# BareBonesArduino.net
KiCad netlist of a schematic drawn in EAGLE
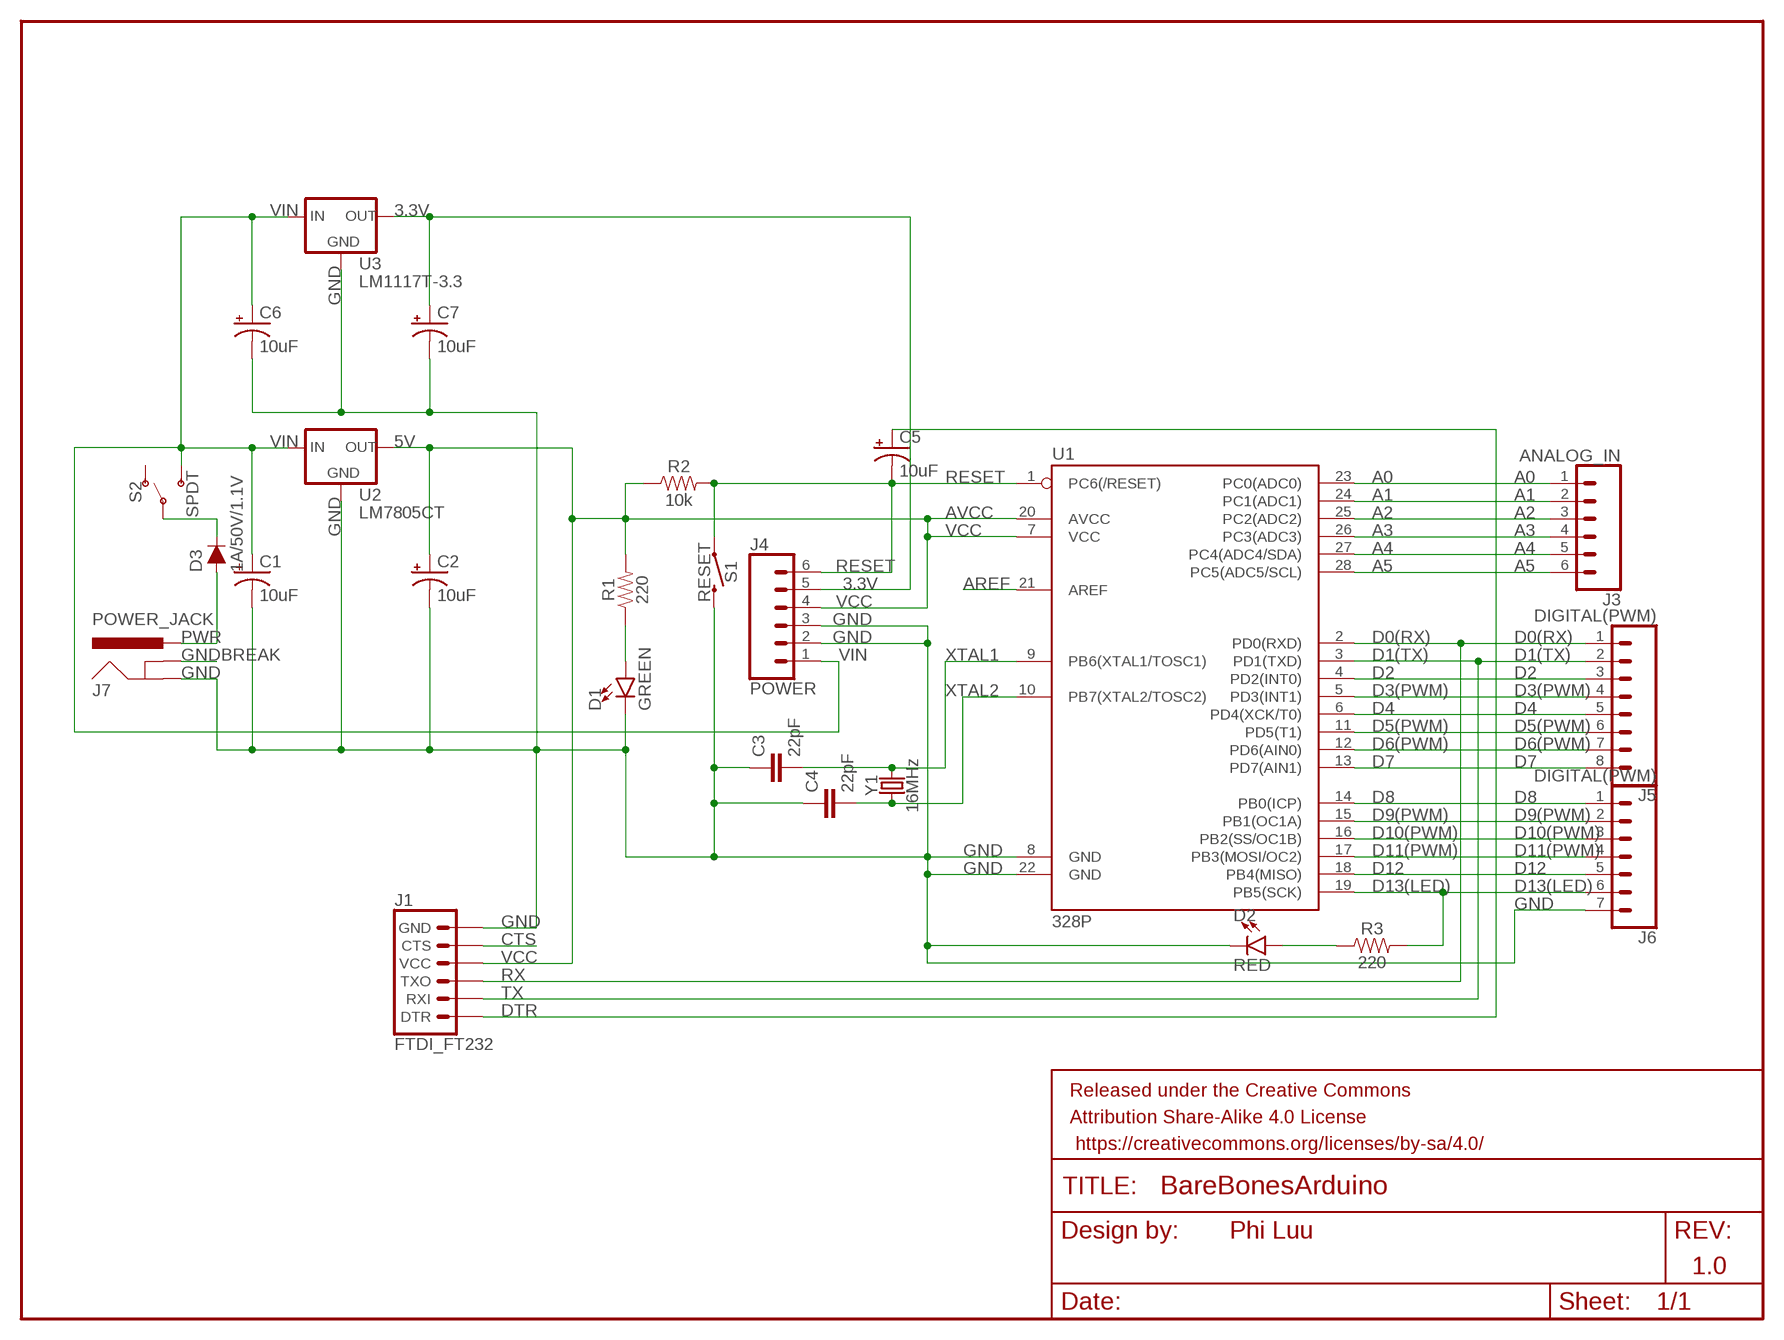
[diagram p0: schematic, sheet 1]

(export (version "E")
  (design (tool "Eeschema 10.0.6"))
  (components
    (comp (ref "C1")
      (value "10uF")
      (footprint "eagle-import:CPOL-RADIAL-2.5MM-5MM")
      (libsource (lib "eagle-import") (part "10UF-POLAR-RADIAL-2.5MM-25V-20%"))
    )
    (comp (ref "C2")
      (value "10uF")
      (footprint "eagle-import:CPOL-RADIAL-2.5MM-5MM")
      (libsource (lib "eagle-import") (part "10UF-POLAR-RADIAL-2.5MM-25V-20%"))
    )
    (comp (ref "C3")
      (value "22pF")
      (footprint "eagle-import:CAP-PTH-2.54")
      (libsource (lib "eagle-import") (part "22PF-PTH-2.54MM-200V-5%"))
    )
    (comp (ref "C4")
      (value "22pF")
      (footprint "eagle-import:CAP-PTH-2.54")
      (libsource (lib "eagle-import") (part "22PF-PTH-2.54MM-200V-5%"))
    )
    (comp (ref "C5")
      (value "10uF")
      (footprint "eagle-import:CPOL-RADIAL-2.5MM-5MM")
      (libsource (lib "eagle-import") (part "10UF-POLAR-RADIAL-2.5MM-25V-20%"))
    )
    (comp (ref "C6")
      (value "10uF")
      (footprint "eagle-import:CPOL-RADIAL-2.5MM-5MM")
      (libsource (lib "eagle-import") (part "10UF-POLAR-RADIAL-2.5MM-25V-20%"))
    )
    (comp (ref "C7")
      (value "10uF")
      (footprint "eagle-import:CPOL-RADIAL-2.5MM-5MM")
      (libsource (lib "eagle-import") (part "10UF-POLAR-RADIAL-2.5MM-25V-20%"))
    )
    (comp (ref "D1")
      (value "GREEN")
      (footprint "eagle-import:LED_5MM")
      (libsource (lib "eagle-import") (part "LED5MM"))
    )
    (comp (ref "D2")
      (value "RED")
      (footprint "eagle-import:LED_5MM")
      (libsource (lib "eagle-import") (part "LED5MM"))
    )
    (comp (ref "D3")
      (value "1A/50V/1.1V")
      (footprint "eagle-import:DIODE-1N4001")
      (libsource (lib "eagle-import") (part "DIODE-PTH"))
    )
    (comp (ref "FRAME1")
      (value "FRAME-LETTER")
      (footprint "eagle-import:CREATIVE_COMMONS")
      (libsource (lib "eagle-import") (part "FRAME-LETTER"))
    )
    (comp (ref "J1")
      (value "FTDI_FT232")
      (footprint "eagle-import:1X06")
      (libsource (lib "eagle-import") (part "6_PIN_SERIAL_TARGET"))
    )
    (comp (ref "J3")
      (value "ANALOG_IN")
      (footprint "eagle-import:1X06")
      (libsource (lib "eagle-import") (part "CONN_06SILK_FEMALE_PTH"))
    )
    (comp (ref "J4")
      (value "POWER")
      (footprint "eagle-import:1X06")
      (libsource (lib "eagle-import") (part "CONN_06SILK_FEMALE_PTH"))
    )
    (comp (ref "J5")
      (value "DIGITAL(PWM)")
      (footprint "eagle-import:1X08")
      (libsource (lib "eagle-import") (part "CONN_08{dblquote}"))
    )
    (comp (ref "J6")
      (value "DIGITAL(PWM)")
      (footprint "eagle-import:1X07")
      (libsource (lib "eagle-import") (part "CONN_07"))
    )
    (comp (ref "J7")
      (value "POWER_JACK")
      (footprint "eagle-import:POWER_JACK_PTH")
      (libsource (lib "eagle-import") (part "POWER_JACK"))
    )
    (comp (ref "R1")
      (value "220")
      (footprint "eagle-import:AXIAL-0.3")
      (libsource (lib "eagle-import") (part "1KOHM-HORIZ-1/4W-5%"))
    )
    (comp (ref "R2")
      (value "10k")
      (footprint "eagle-import:AXIAL-0.3")
      (libsource (lib "eagle-import") (part "10KOHM-HORIZ-1/4W-5%"))
    )
    (comp (ref "R3")
      (value "220")
      (footprint "eagle-import:AXIAL-0.3")
      (libsource (lib "eagle-import") (part "1KOHM-HORIZ-1/4W-5%"))
    )
    (comp (ref "S1")
      (value "RESET")
      (footprint "eagle-import:TACTILE_SWITCH_PTH_6.0MM")
      (libsource (lib "eagle-import") (part "MOMENTARY-SWITCH-SPST-PTH-6.0MM"))
    )
    (comp (ref "S2")
      (value "SPDT")
      (footprint "eagle-import:SWITCH_SPDT_PTH_11.6X4.0MM")
      (libsource (lib "eagle-import") (part "SWITCH-SPDT-PTH-11.6X4.0MM"))
    )
    (comp (ref "U1")
      (value "328P")
      (footprint "eagle-import:DIP28")
      (libsource (lib "eagle-import") (part "ATMEGA328P_PDIP"))
    )
    (comp (ref "U2")
      (value "LM7805CT")
      (footprint "eagle-import:TO-220-ALT")
      (libsource (lib "eagle-import") (part "V_REG_78XX-TO-220"))
    )
    (comp (ref "U3")
      (value "LM1117T-3.3")
      (footprint "eagle-import:78XXL")
      (libsource (lib "eagle-import") (part "V_REG_LD1117VXX"))
    )
    (comp (ref "Y1")
      (value "16MHz")
      (footprint "eagle-import:HC49US")
      (libsource (lib "eagle-import") (part "CRYSTAL-16MHZPTH-HC49US"))
    )
  )
  (nets
    (net (code "1") (name "/3.3V") (class "Default")
      (node (ref "C7") (pin "1") (pinfunction "+_1") (pintype "passive"))
      (node (ref "J4") (pin "5") (pinfunction "5_5") (pintype "passive"))
      (node (ref "U3") (pin "GND") (pinfunction "OUT_GND") (pintype "passive"))
    )
    (net (code "2") (name "/A0") (class "Default")
      (node (ref "J3") (pin "1") (pinfunction "1_1") (pintype "passive"))
      (node (ref "U1") (pin "23") (pinfunction "PC0(ADC0)_23") (pintype "bidirectional"))
    )
    (net (code "3") (name "/A1") (class "Default")
      (node (ref "J3") (pin "2") (pinfunction "2_2") (pintype "passive"))
      (node (ref "U1") (pin "24") (pinfunction "PC1(ADC1)_24") (pintype "bidirectional"))
    )
    (net (code "4") (name "/A2") (class "Default")
      (node (ref "J3") (pin "3") (pinfunction "3_3") (pintype "passive"))
      (node (ref "U1") (pin "25") (pinfunction "PC2(ADC2)_25") (pintype "bidirectional"))
    )
    (net (code "5") (name "/A3") (class "Default")
      (node (ref "J3") (pin "4") (pinfunction "4_4") (pintype "passive"))
      (node (ref "U1") (pin "26") (pinfunction "PC3(ADC3)_26") (pintype "bidirectional"))
    )
    (net (code "6") (name "/A4") (class "Default")
      (node (ref "J3") (pin "5") (pinfunction "5_5") (pintype "passive"))
      (node (ref "U1") (pin "27") (pinfunction "PC4(ADC4/SDA)_27") (pintype "bidirectional"))
    )
    (net (code "7") (name "/A5") (class "Default")
      (node (ref "J3") (pin "6") (pinfunction "6_6") (pintype "passive"))
      (node (ref "U1") (pin "28") (pinfunction "PC5(ADC5/SCL)_28") (pintype "bidirectional"))
    )
    (net (code "8") (name "/AREF") (class "Default")
      (node (ref "U1") (pin "21") (pinfunction "AREF_21") (pintype "bidirectional"))
    )
    (net (code "9") (name "/CTS") (class "Default")
      (node (ref "J1") (pin "5") (pinfunction "CTS_5") (pintype "passive"))
    )
    (net (code "10") (name "/D0(RX)") (class "Default")
      (node (ref "J1") (pin "3") (pinfunction "TXO_3") (pintype "passive"))
      (node (ref "J5") (pin "1") (pinfunction "1_1") (pintype "passive"))
      (node (ref "U1") (pin "2") (pinfunction "PD0(RXD)_2") (pintype "bidirectional"))
    )
    (net (code "11") (name "/D1(TX)") (class "Default")
      (node (ref "J1") (pin "2") (pinfunction "RXI_2") (pintype "passive"))
      (node (ref "J5") (pin "2") (pinfunction "2_2") (pintype "passive"))
      (node (ref "U1") (pin "3") (pinfunction "PD1(TXD)_3") (pintype "bidirectional"))
    )
    (net (code "12") (name "/D2") (class "Default")
      (node (ref "J5") (pin "3") (pinfunction "3_3") (pintype "passive"))
      (node (ref "U1") (pin "4") (pinfunction "PD2(INT0)_4") (pintype "bidirectional"))
    )
    (net (code "13") (name "/D3(PWM)") (class "Default")
      (node (ref "J5") (pin "4") (pinfunction "4_4") (pintype "passive"))
      (node (ref "U1") (pin "5") (pinfunction "PD3(INT1)_5") (pintype "bidirectional"))
    )
    (net (code "14") (name "/D4") (class "Default")
      (node (ref "J5") (pin "5") (pinfunction "5_5") (pintype "passive"))
      (node (ref "U1") (pin "6") (pinfunction "PD4(XCK/T0)_6") (pintype "bidirectional"))
    )
    (net (code "15") (name "/D5(PWM)") (class "Default")
      (node (ref "J5") (pin "6") (pinfunction "6_6") (pintype "passive"))
      (node (ref "U1") (pin "11") (pinfunction "PD5(T1)_11") (pintype "bidirectional"))
    )
    (net (code "16") (name "/D6(PWM)") (class "Default")
      (node (ref "J5") (pin "7") (pinfunction "7_7") (pintype "passive"))
      (node (ref "U1") (pin "12") (pinfunction "PD6(AIN0)_12") (pintype "bidirectional"))
    )
    (net (code "17") (name "/D7") (class "Default")
      (node (ref "J5") (pin "8") (pinfunction "8_8") (pintype "passive"))
      (node (ref "U1") (pin "13") (pinfunction "PD7(AIN1)_13") (pintype "bidirectional"))
    )
    (net (code "18") (name "/D8") (class "Default")
      (node (ref "J6") (pin "1") (pinfunction "1_1") (pintype "passive"))
      (node (ref "U1") (pin "14") (pinfunction "PB0(ICP)_14") (pintype "bidirectional"))
    )
    (net (code "19") (name "/D9(PWM)") (class "Default")
      (node (ref "J6") (pin "2") (pinfunction "2_2") (pintype "passive"))
      (node (ref "U1") (pin "15") (pinfunction "PB1(OC1A)_15") (pintype "bidirectional"))
    )
    (net (code "20") (name "/D10(PWM)") (class "Default")
      (node (ref "J6") (pin "3") (pinfunction "3_3") (pintype "passive"))
      (node (ref "U1") (pin "16") (pinfunction "PB2(SS/OC1B)_16") (pintype "bidirectional"))
    )
    (net (code "21") (name "/D11(PWM)") (class "Default")
      (node (ref "J6") (pin "4") (pinfunction "4_4") (pintype "passive"))
      (node (ref "U1") (pin "17") (pinfunction "PB3(MOSI/OC2)_17") (pintype "bidirectional"))
    )
    (net (code "22") (name "/D12") (class "Default")
      (node (ref "J6") (pin "5") (pinfunction "5_5") (pintype "passive"))
      (node (ref "U1") (pin "18") (pinfunction "PB4(MISO)_18") (pintype "bidirectional"))
    )
    (net (code "23") (name "/D13(LED)") (class "Default")
      (node (ref "J6") (pin "6") (pinfunction "6_6") (pintype "passive"))
      (node (ref "R3") (pin "P$2") (pinfunction "2_P$2") (pintype "passive"))
      (node (ref "U1") (pin "19") (pinfunction "PB5(SCK)_19") (pintype "bidirectional"))
    )
    (net (code "24") (name "/DTR") (class "Default")
      (node (ref "C5") (pin "1") (pinfunction "+_1") (pintype "passive"))
      (node (ref "J1") (pin "1") (pinfunction "DTR_1") (pintype "passive"))
    )
    (net (code "25") (name "/GND") (class "Default")
      (node (ref "C1") (pin "2") (pinfunction "-_2") (pintype "passive"))
      (node (ref "C2") (pin "2") (pinfunction "-_2") (pintype "passive"))
      (node (ref "C3") (pin "1") (pinfunction "1_1") (pintype "passive"))
      (node (ref "C4") (pin "1") (pinfunction "1_1") (pintype "passive"))
      (node (ref "C6") (pin "2") (pinfunction "-_2") (pintype "passive"))
      (node (ref "C7") (pin "2") (pinfunction "-_2") (pintype "passive"))
      (node (ref "D1") (pin "K") (pinfunction "C_K") (pintype "passive"))
      (node (ref "D2") (pin "K") (pinfunction "C_K") (pintype "passive"))
      (node (ref "J1") (pin "6") (pinfunction "GND_6") (pintype "passive"))
      (node (ref "J4") (pin "2") (pinfunction "2_2") (pintype "passive"))
      (node (ref "J4") (pin "3") (pinfunction "3_3") (pintype "passive"))
      (node (ref "J6") (pin "7") (pinfunction "7_7") (pintype "passive"))
      (node (ref "J7") (pin "GND") (pinfunction "GND_GND") (pintype "bidirectional"))
      (node (ref "S1") (pin "3") (pinfunction "2_3") (pintype "passive"))
      (node (ref "U1") (pin "22") (pinfunction "GND_22") (pintype "bidirectional"))
      (node (ref "U1") (pin "8") (pinfunction "GND_8") (pintype "bidirectional"))
      (node (ref "U2") (pin "GND") (pinfunction "GND_GND") (pintype "input"))
      (node (ref "U3") (pin "IN") (pinfunction "GND_IN") (pintype "input"))
    )
    (net (code "26") (name "/GNDBREAK") (class "Default")
      (node (ref "J7") (pin "GNDBREAK") (pinfunction "GNDBREAK_GNDBREAK") (pintype "bidirectional"))
    )
    (net (code "27") (name "/PWR") (class "Default")
      (node (ref "D3") (pin "A") (pinfunction "A_A") (pintype "passive"))
      (node (ref "J7") (pin "PWR") (pinfunction "PWR_PWR") (pintype "bidirectional"))
    )
    (net (code "28") (name "/RESET") (class "Default")
      (node (ref "C5") (pin "2") (pinfunction "-_2") (pintype "passive"))
      (node (ref "J4") (pin "6") (pinfunction "6_6") (pintype "passive"))
      (node (ref "R2") (pin "P$2") (pinfunction "2_P$2") (pintype "passive"))
      (node (ref "S1") (pin "1") (pinfunction "1_1") (pintype "passive"))
      (node (ref "U1") (pin "1") (pinfunction "PC6(/RESET)_1") (pintype "bidirectional"))
    )
    (net (code "29") (name "/VCC") (class "Default")
      (node (ref "C2") (pin "1") (pinfunction "+_1") (pintype "passive"))
      (node (ref "J1") (pin "4") (pinfunction "VCC_4") (pintype "passive"))
      (node (ref "J4") (pin "4") (pinfunction "4_4") (pintype "passive"))
      (node (ref "R1") (pin "P$2") (pinfunction "2_P$2") (pintype "passive"))
      (node (ref "R2") (pin "P$1") (pinfunction "1_P$1") (pintype "passive"))
      (node (ref "U1") (pin "20") (pinfunction "AVCC_20") (pintype "bidirectional"))
      (node (ref "U1") (pin "7") (pinfunction "VCC_7") (pintype "bidirectional"))
      (node (ref "U2") (pin "OUT") (pinfunction "OUT_OUT") (pintype "passive"))
    )
    (net (code "30") (name "/VIN") (class "Default")
      (node (ref "C1") (pin "1") (pinfunction "+_1") (pintype "passive"))
      (node (ref "C6") (pin "1") (pinfunction "+_1") (pintype "passive"))
      (node (ref "J4") (pin "1") (pinfunction "1_1") (pintype "passive"))
      (node (ref "S2") (pin "3") (pinfunction "S_3") (pintype "passive"))
      (node (ref "U2") (pin "IN") (pinfunction "IN_IN") (pintype "input"))
      (node (ref "U3") (pin "OUT") (pinfunction "IN_OUT") (pintype "input"))
    )
    (net (code "31") (name "/XTAL1") (class "Default")
      (node (ref "C3") (pin "2") (pinfunction "2_2") (pintype "passive"))
      (node (ref "U1") (pin "9") (pinfunction "PB6(XTAL1/TOSC1)_9") (pintype "bidirectional"))
      (node (ref "Y1") (pin "2") (pinfunction "2_2") (pintype "passive"))
    )
    (net (code "32") (name "/XTAL2") (class "Default")
      (node (ref "C4") (pin "2") (pinfunction "2_2") (pintype "passive"))
      (node (ref "U1") (pin "10") (pinfunction "PB7(XTAL2/TOSC2)_10") (pintype "bidirectional"))
      (node (ref "Y1") (pin "1") (pinfunction "1_1") (pintype "passive"))
    )
    (net (code "33") (name "Net-(R1-1)") (class "Default")
      (node (ref "D1") (pin "A") (pinfunction "A_A") (pintype "passive"))
      (node (ref "R1") (pin "P$1") (pinfunction "1_P$1") (pintype "passive"))
    )
    (net (code "34") (name "Net-(R3-1)") (class "Default")
      (node (ref "D2") (pin "A") (pinfunction "A_A") (pintype "passive"))
      (node (ref "R3") (pin "P$1") (pinfunction "1_P$1") (pintype "passive"))
    )
    (net (code "35") (name "Net-(S2-P)") (class "Default")
      (node (ref "D3") (pin "C") (pinfunction "C_C") (pintype "passive"))
      (node (ref "S2") (pin "2") (pinfunction "P_2") (pintype "passive"))
    )
    (net (code "36") (name "unconnected-(S2-O-Pad1)") (class "Default")
      (node (ref "S2") (pin "1") (pinfunction "O_1") (pintype "passive"))
    )
  )
)
